# placa_v1.net
KiCad netlist of a schematic drawn in EAGLE
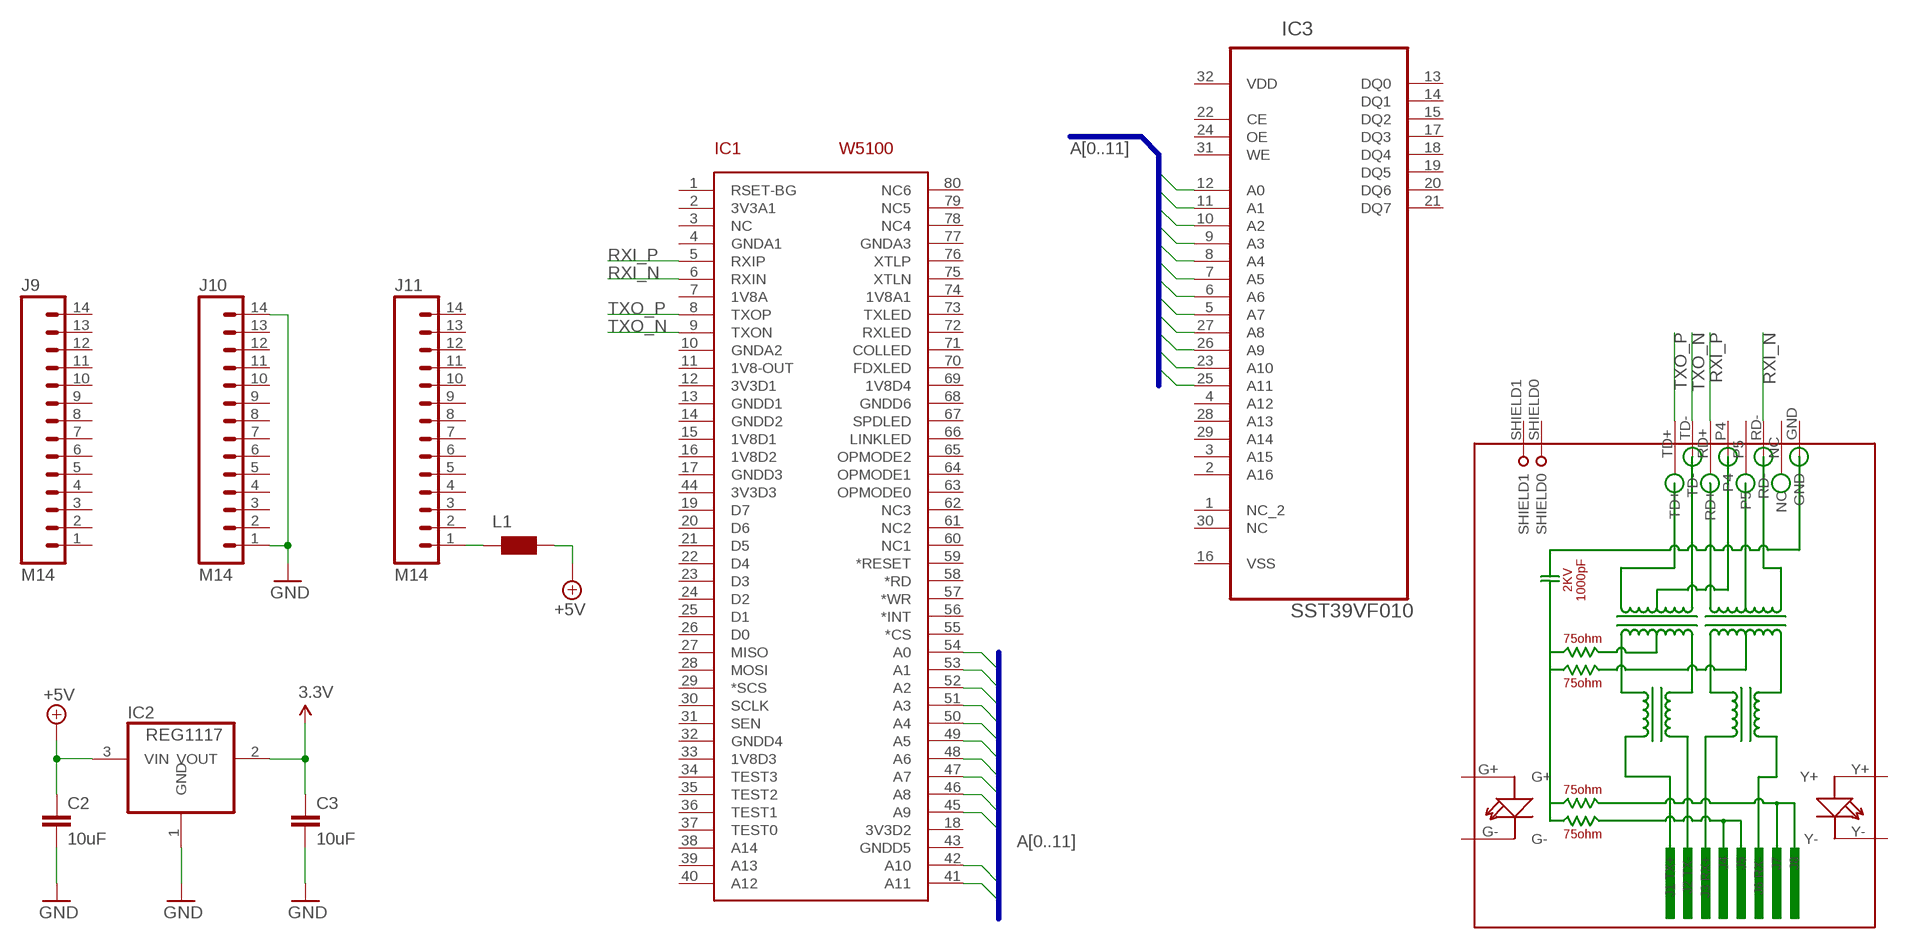
[diagram p0: schematic, sheet 1]

(export (version "E")
  (design (tool "Eeschema 10.0.6"))
  (components
    (comp (ref "C2")
      (value "10uF")
      (footprint "eagle-import:C0805K")
      (libsource (lib "eagle-import") (part "C-EUC0805K"))
    )
    (comp (ref "C3")
      (value "10uF")
      (footprint "eagle-import:C0805K")
      (libsource (lib "eagle-import") (part "C-EUC0805K"))
    )
    (comp (ref "IC1")
      (value "W5100")
      (footprint "eagle-import:SQFP-S-10X10-80")
      (libsource (lib "eagle-import") (part "W5100"))
    )
    (comp (ref "IC2")
      (value "REG1117")
      (footprint "eagle-import:SOT223")
      (libsource (lib "eagle-import") (part "REG1117"))
    )
    (comp (ref "IC3")
      (value "SST39VF010")
      (footprint "eagle-import:PLCC127P1244X1498X357-32N")
      (fields (field (name "MPN") "SST39VF010-70-4I-NHE"))
      (libsource (lib "eagle-import") (part "SST39VF010-70-4I-NHE"))
    )
    (comp (ref "J9")
      (value "M14")
      (footprint "eagle-import:1X14")
      (libsource (lib "eagle-import") (part "M14"))
    )
    (comp (ref "J10")
      (value "M14")
      (footprint "eagle-import:1X14")
      (libsource (lib "eagle-import") (part "M14"))
    )
    (comp (ref "J11")
      (value "M14")
      (footprint "eagle-import:1X14")
      (libsource (lib "eagle-import") (part "M14"))
    )
    (comp (ref "L1")
      (value "WE-CBF_0805")
      (footprint "eagle-import:0805")
      (libsource (lib "eagle-import") (part "WE-CBF_0805"))
    )
    (comp (ref "RJ1")
      (value "HR911105A")
      (footprint "eagle-import:HR911105A")
      (libsource (lib "eagle-import") (part "HR911105A"))
    )
  )
  (nets
    (net (code "1") (name "+5V") (class "Default")
      (node (ref "C2") (pin "1") (pinfunction "1_1") (pintype "passive"))
      (node (ref "IC2") (pin "3") (pinfunction "VIN_3") (pintype "input"))
      (node (ref "L1") (pin "2") (pinfunction "2_2") (pintype "passive"))
    )
    (net (code "2") (name "/1V8-OUT") (class "Default")
      (node (ref "IC1") (pin "11") (pinfunction "1V8-OUT_11") (pintype "power_in"))
    )
    (net (code "3") (name "/1V8A") (class "Default")
      (node (ref "IC1") (pin "7") (pinfunction "1V8A_7") (pintype "power_in"))
    )
    (net (code "4") (name "/1V8A1") (class "Default")
      (node (ref "IC1") (pin "74") (pinfunction "1V8A1_74") (pintype "power_in"))
    )
    (net (code "5") (name "/1V8D1") (class "Default")
      (node (ref "IC1") (pin "15") (pinfunction "1V8D1_15") (pintype "power_in"))
    )
    (net (code "6") (name "/1V8D2") (class "Default")
      (node (ref "IC1") (pin "16") (pinfunction "1V8D2_16") (pintype "power_in"))
    )
    (net (code "7") (name "/1V8D3") (class "Default")
      (node (ref "IC1") (pin "33") (pinfunction "1V8D3_33") (pintype "power_in"))
    )
    (net (code "8") (name "/1V8D4") (class "Default")
      (node (ref "IC1") (pin "69") (pinfunction "1V8D4_69") (pintype "power_in"))
    )
    (net (code "9") (name "/3V3A1") (class "Default")
      (node (ref "IC1") (pin "2") (pinfunction "3V3A1_2") (pintype "power_in"))
    )
    (net (code "10") (name "/3V3D1") (class "Default")
      (node (ref "IC1") (pin "12") (pinfunction "3V3D1_12") (pintype "power_in"))
    )
    (net (code "11") (name "/3V3D2") (class "Default")
      (node (ref "IC1") (pin "18") (pinfunction "3V3D2_18") (pintype "power_in"))
    )
    (net (code "12") (name "/3V3D3") (class "Default")
      (node (ref "IC1") (pin "44") (pinfunction "3V3D3_44") (pintype "power_in"))
    )
    (net (code "13") (name "/A0") (class "Default")
      (node (ref "IC1") (pin "54") (pinfunction "A0_54") (pintype "input"))
      (node (ref "IC3") (pin "12") (pinfunction "A0_12") (pintype "input"))
    )
    (net (code "14") (name "/A1") (class "Default")
      (node (ref "IC1") (pin "53") (pinfunction "A1_53") (pintype "input"))
      (node (ref "IC3") (pin "11") (pinfunction "A1_11") (pintype "input"))
    )
    (net (code "15") (name "/A2") (class "Default")
      (node (ref "IC1") (pin "52") (pinfunction "A2_52") (pintype "input"))
      (node (ref "IC3") (pin "10") (pinfunction "A2_10") (pintype "input"))
    )
    (net (code "16") (name "/A3") (class "Default")
      (node (ref "IC1") (pin "51") (pinfunction "A3_51") (pintype "input"))
      (node (ref "IC3") (pin "9") (pinfunction "A3_9") (pintype "input"))
    )
    (net (code "17") (name "/A4") (class "Default")
      (node (ref "IC1") (pin "50") (pinfunction "A4_50") (pintype "input"))
      (node (ref "IC3") (pin "8") (pinfunction "A4_8") (pintype "input"))
    )
    (net (code "18") (name "/A5") (class "Default")
      (node (ref "IC1") (pin "49") (pinfunction "A5_49") (pintype "input"))
      (node (ref "IC3") (pin "7") (pinfunction "A5_7") (pintype "input"))
    )
    (net (code "19") (name "/A6") (class "Default")
      (node (ref "IC1") (pin "48") (pinfunction "A6_48") (pintype "input"))
      (node (ref "IC3") (pin "6") (pinfunction "A6_6") (pintype "input"))
    )
    (net (code "20") (name "/A7") (class "Default")
      (node (ref "IC1") (pin "47") (pinfunction "A7_47") (pintype "input"))
      (node (ref "IC3") (pin "5") (pinfunction "A7_5") (pintype "input"))
    )
    (net (code "21") (name "/A8") (class "Default")
      (node (ref "IC1") (pin "46") (pinfunction "A8_46") (pintype "input"))
      (node (ref "IC3") (pin "27") (pinfunction "A8_27") (pintype "input"))
    )
    (net (code "22") (name "/A9") (class "Default")
      (node (ref "IC1") (pin "45") (pinfunction "A9_45") (pintype "input"))
      (node (ref "IC3") (pin "26") (pinfunction "A9_26") (pintype "input"))
    )
    (net (code "23") (name "/A10") (class "Default")
      (node (ref "IC1") (pin "42") (pinfunction "A10_42") (pintype "input"))
      (node (ref "IC3") (pin "23") (pinfunction "A10_23") (pintype "input"))
    )
    (net (code "24") (name "/A11") (class "Default")
      (node (ref "IC1") (pin "41") (pinfunction "A11_41") (pintype "input"))
      (node (ref "IC3") (pin "25") (pinfunction "A11_25") (pintype "input"))
    )
    (net (code "26") (name "/GNDA1") (class "Default")
      (node (ref "IC1") (pin "4") (pinfunction "GNDA1_4") (pintype "power_in"))
    )
    (net (code "27") (name "/GNDA2") (class "Default")
      (node (ref "IC1") (pin "10") (pinfunction "GNDA2_10") (pintype "power_in"))
    )
    (net (code "28") (name "/GNDA3") (class "Default")
      (node (ref "IC1") (pin "77") (pinfunction "GNDA3_77") (pintype "power_in"))
    )
    (net (code "29") (name "/GNDD1") (class "Default")
      (node (ref "IC1") (pin "13") (pinfunction "GNDD1_13") (pintype "power_in"))
    )
    (net (code "30") (name "/GNDD2") (class "Default")
      (node (ref "IC1") (pin "14") (pinfunction "GNDD2_14") (pintype "power_in"))
    )
    (net (code "31") (name "/GNDD3") (class "Default")
      (node (ref "IC1") (pin "17") (pinfunction "GNDD3_17") (pintype "power_in"))
    )
    (net (code "32") (name "/GNDD4") (class "Default")
      (node (ref "IC1") (pin "32") (pinfunction "GNDD4_32") (pintype "power_in"))
    )
    (net (code "33") (name "/GNDD5") (class "Default")
      (node (ref "IC1") (pin "43") (pinfunction "GNDD5_43") (pintype "power_in"))
    )
    (net (code "34") (name "/GNDD6") (class "Default")
      (node (ref "IC1") (pin "68") (pinfunction "GNDD6_68") (pintype "power_in"))
    )
    (net (code "35") (name "/RXI_N") (class "Default")
      (node (ref "IC1") (pin "6") (pinfunction "RXIN_6") (pintype "input"))
      (node (ref "RJ1") (pin "RD-") (pinfunction "RD-_RD-") (pintype "bidirectional"))
    )
    (net (code "36") (name "/RXI_P") (class "Default")
      (node (ref "IC1") (pin "5") (pinfunction "RXIP_5") (pintype "input"))
      (node (ref "RJ1") (pin "RD+") (pinfunction "RD+_RD+") (pintype "bidirectional"))
    )
    (net (code "37") (name "/TXO_N") (class "Default")
      (node (ref "IC1") (pin "9") (pinfunction "TXON_9") (pintype "output"))
      (node (ref "RJ1") (pin "TD-") (pinfunction "TD-_TD-") (pintype "bidirectional"))
    )
    (net (code "38") (name "/TXO_P") (class "Default")
      (node (ref "IC1") (pin "8") (pinfunction "TXOP_8") (pintype "output"))
      (node (ref "RJ1") (pin "TD+") (pinfunction "TD+_TD+") (pintype "bidirectional"))
    )
    (net (code "39") (name "/VDD") (class "Default")
      (node (ref "IC3") (pin "32") (pinfunction "VDD_32") (pintype "power_in"))
    )
    (net (code "40") (name "3.3V") (class "Default")
      (node (ref "C3") (pin "1") (pinfunction "1_1") (pintype "passive"))
      (node (ref "IC2") (pin "2") (pinfunction "VOUT_2") (pintype "output"))
    )
    (net (code "41") (name "GND") (class "Default")
      (node (ref "C2") (pin "2") (pinfunction "2_2") (pintype "passive"))
      (node (ref "C3") (pin "2") (pinfunction "2_2") (pintype "passive"))
      (node (ref "IC2") (pin "1") (pinfunction "GND_1") (pintype "power_in"))
      (node (ref "J10") (pin "1") (pinfunction "1_1") (pintype "passive"))
      (node (ref "J10") (pin "14") (pinfunction "14_14") (pintype "passive"))
    )
    (net (code "42") (name "Net-(J11-Pad1)") (class "Default")
      (node (ref "J11") (pin "1") (pinfunction "1_1") (pintype "passive"))
      (node (ref "L1") (pin "1") (pinfunction "1_1") (pintype "passive"))
    )
    (net (code "43") (name "unconnected-(IC1-*CS-Pad55)") (class "Default")
      (node (ref "IC1") (pin "55") (pinfunction "*CS_55") (pintype "input"))
    )
    (net (code "44") (name "unconnected-(IC1-*INT-Pad56)") (class "Default")
      (node (ref "IC1") (pin "56") (pinfunction "*INT_56") (pintype "input"))
    )
    (net (code "45") (name "unconnected-(IC1-*RD-Pad58)") (class "Default")
      (node (ref "IC1") (pin "58") (pinfunction "*RD_58") (pintype "input"))
    )
    (net (code "46") (name "unconnected-(IC1-*RESET-Pad59)") (class "Default")
      (node (ref "IC1") (pin "59") (pinfunction "*RESET_59") (pintype "input"))
    )
    (net (code "47") (name "unconnected-(IC1-*SCS-Pad29)") (class "Default")
      (node (ref "IC1") (pin "29") (pinfunction "*SCS_29") (pintype "input"))
    )
    (net (code "48") (name "unconnected-(IC1-*WR-Pad57)") (class "Default")
      (node (ref "IC1") (pin "57") (pinfunction "*WR_57") (pintype "input"))
    )
    (net (code "49") (name "unconnected-(IC1-A12-Pad40)") (class "Default")
      (node (ref "IC1") (pin "40") (pinfunction "A12_40") (pintype "input"))
    )
    (net (code "50") (name "unconnected-(IC1-A13-Pad39)") (class "Default")
      (node (ref "IC1") (pin "39") (pinfunction "A13_39") (pintype "input"))
    )
    (net (code "51") (name "unconnected-(IC1-A14-Pad38)") (class "Default")
      (node (ref "IC1") (pin "38") (pinfunction "A14_38") (pintype "input"))
    )
    (net (code "52") (name "unconnected-(IC1-COLLED-Pad71)") (class "Default")
      (node (ref "IC1") (pin "71") (pinfunction "COLLED_71") (pintype "output"))
    )
    (net (code "53") (name "unconnected-(IC1-D0-Pad26)") (class "Default")
      (node (ref "IC1") (pin "26") (pinfunction "D0_26") (pintype "input"))
    )
    (net (code "54") (name "unconnected-(IC1-D1-Pad25)") (class "Default")
      (node (ref "IC1") (pin "25") (pinfunction "D1_25") (pintype "input"))
    )
    (net (code "55") (name "unconnected-(IC1-D2-Pad24)") (class "Default")
      (node (ref "IC1") (pin "24") (pinfunction "D2_24") (pintype "input"))
    )
    (net (code "56") (name "unconnected-(IC1-D3-Pad23)") (class "Default")
      (node (ref "IC1") (pin "23") (pinfunction "D3_23") (pintype "input"))
    )
    (net (code "57") (name "unconnected-(IC1-D4-Pad22)") (class "Default")
      (node (ref "IC1") (pin "22") (pinfunction "D4_22") (pintype "input"))
    )
    (net (code "58") (name "unconnected-(IC1-D5-Pad21)") (class "Default")
      (node (ref "IC1") (pin "21") (pinfunction "D5_21") (pintype "input"))
    )
    (net (code "59") (name "unconnected-(IC1-D6-Pad20)") (class "Default")
      (node (ref "IC1") (pin "20") (pinfunction "D6_20") (pintype "input"))
    )
    (net (code "60") (name "unconnected-(IC1-D7-Pad19)") (class "Default")
      (node (ref "IC1") (pin "19") (pinfunction "D7_19") (pintype "input"))
    )
    (net (code "61") (name "unconnected-(IC1-FDXLED-Pad70)") (class "Default")
      (node (ref "IC1") (pin "70") (pinfunction "FDXLED_70") (pintype "output"))
    )
    (net (code "62") (name "unconnected-(IC1-LINKLED-Pad66)") (class "Default")
      (node (ref "IC1") (pin "66") (pinfunction "LINKLED_66") (pintype "output"))
    )
    (net (code "63") (name "unconnected-(IC1-MISO-Pad27)") (class "Default")
      (node (ref "IC1") (pin "27") (pinfunction "MISO_27") (pintype "input"))
    )
    (net (code "64") (name "unconnected-(IC1-MOSI-Pad28)") (class "Default")
      (node (ref "IC1") (pin "28") (pinfunction "MOSI_28") (pintype "output"))
    )
    (net (code "65") (name "unconnected-(IC1-NC-Pad3)") (class "Default")
      (node (ref "IC1") (pin "3") (pinfunction "NC_3") (pintype "no_connect"))
    )
    (net (code "66") (name "unconnected-(IC1-NC1-Pad60)") (class "Default")
      (node (ref "IC1") (pin "60") (pinfunction "NC1_60") (pintype "no_connect"))
    )
    (net (code "67") (name "unconnected-(IC1-NC2-Pad61)") (class "Default")
      (node (ref "IC1") (pin "61") (pinfunction "NC2_61") (pintype "no_connect"))
    )
    (net (code "68") (name "unconnected-(IC1-NC3-Pad62)") (class "Default")
      (node (ref "IC1") (pin "62") (pinfunction "NC3_62") (pintype "no_connect"))
    )
    (net (code "69") (name "unconnected-(IC1-NC4-Pad78)") (class "Default")
      (node (ref "IC1") (pin "78") (pinfunction "NC4_78") (pintype "no_connect"))
    )
    (net (code "70") (name "unconnected-(IC1-NC5-Pad79)") (class "Default")
      (node (ref "IC1") (pin "79") (pinfunction "NC5_79") (pintype "no_connect"))
    )
    (net (code "71") (name "unconnected-(IC1-NC6-Pad80)") (class "Default")
      (node (ref "IC1") (pin "80") (pinfunction "NC6_80") (pintype "no_connect"))
    )
    (net (code "72") (name "unconnected-(IC1-OPMODE0-Pad63)") (class "Default")
      (node (ref "IC1") (pin "63") (pinfunction "OPMODE0_63") (pintype "input"))
    )
    (net (code "73") (name "unconnected-(IC1-OPMODE1-Pad64)") (class "Default")
      (node (ref "IC1") (pin "64") (pinfunction "OPMODE1_64") (pintype "input"))
    )
    (net (code "74") (name "unconnected-(IC1-OPMODE2-Pad65)") (class "Default")
      (node (ref "IC1") (pin "65") (pinfunction "OPMODE2_65") (pintype "input"))
    )
    (net (code "75") (name "unconnected-(IC1-RSET-BG-Pad1)") (class "Default")
      (node (ref "IC1") (pin "1") (pinfunction "RSET-BG_1") (pintype "input"))
    )
    (net (code "76") (name "unconnected-(IC1-RXLED-Pad72)") (class "Default")
      (node (ref "IC1") (pin "72") (pinfunction "RXLED_72") (pintype "output"))
    )
    (net (code "77") (name "unconnected-(IC1-SCLK-Pad30)") (class "Default")
      (node (ref "IC1") (pin "30") (pinfunction "SCLK_30") (pintype "input"))
    )
    (net (code "78") (name "unconnected-(IC1-SEN-Pad31)") (class "Default")
      (node (ref "IC1") (pin "31") (pinfunction "SEN_31") (pintype "input"))
    )
    (net (code "79") (name "unconnected-(IC1-SPDLED-Pad67)") (class "Default")
      (node (ref "IC1") (pin "67") (pinfunction "SPDLED_67") (pintype "output"))
    )
    (net (code "80") (name "unconnected-(IC1-TEST0-Pad37)") (class "Default")
      (node (ref "IC1") (pin "37") (pinfunction "TEST0_37") (pintype "input"))
    )
    (net (code "81") (name "unconnected-(IC1-TEST1-Pad36)") (class "Default")
      (node (ref "IC1") (pin "36") (pinfunction "TEST1_36") (pintype "input"))
    )
    (net (code "82") (name "unconnected-(IC1-TEST2-Pad35)") (class "Default")
      (node (ref "IC1") (pin "35") (pinfunction "TEST2_35") (pintype "input"))
    )
    (net (code "83") (name "unconnected-(IC1-TEST3-Pad34)") (class "Default")
      (node (ref "IC1") (pin "34") (pinfunction "TEST3_34") (pintype "input"))
    )
    (net (code "84") (name "unconnected-(IC1-TXLED-Pad73)") (class "Default")
      (node (ref "IC1") (pin "73") (pinfunction "TXLED_73") (pintype "output"))
    )
    (net (code "85") (name "unconnected-(IC1-XTLN-Pad75)") (class "Default")
      (node (ref "IC1") (pin "75") (pinfunction "XTLN_75") (pintype "output"))
    )
    (net (code "86") (name "unconnected-(IC1-XTLP-Pad76)") (class "Default")
      (node (ref "IC1") (pin "76") (pinfunction "XTLP_76") (pintype "output"))
    )
    (net (code "87") (name "unconnected-(IC3-A12-Pad4)") (class "Default")
      (node (ref "IC3") (pin "4") (pinfunction "A12_4") (pintype "input"))
    )
    (net (code "88") (name "unconnected-(IC3-A13-Pad28)") (class "Default")
      (node (ref "IC3") (pin "28") (pinfunction "A13_28") (pintype "input"))
    )
    (net (code "89") (name "unconnected-(IC3-A14-Pad29)") (class "Default")
      (node (ref "IC3") (pin "29") (pinfunction "A14_29") (pintype "input"))
    )
    (net (code "90") (name "unconnected-(IC3-A15-Pad3)") (class "Default")
      (node (ref "IC3") (pin "3") (pinfunction "A15_3") (pintype "input"))
    )
    (net (code "91") (name "unconnected-(IC3-A16-Pad2)") (class "Default")
      (node (ref "IC3") (pin "2") (pinfunction "A16_2") (pintype "input"))
    )
    (net (code "92") (name "unconnected-(IC3-CE-Pad22)") (class "Default")
      (node (ref "IC3") (pin "22") (pinfunction "CE_22") (pintype "input"))
    )
    (net (code "93") (name "unconnected-(IC3-DQ0-Pad13)") (class "Default")
      (node (ref "IC3") (pin "13") (pinfunction "DQ0_13") (pintype "output"))
    )
    (net (code "94") (name "unconnected-(IC3-DQ1-Pad14)") (class "Default")
      (node (ref "IC3") (pin "14") (pinfunction "DQ1_14") (pintype "output"))
    )
    (net (code "95") (name "unconnected-(IC3-DQ2-Pad15)") (class "Default")
      (node (ref "IC3") (pin "15") (pinfunction "DQ2_15") (pintype "output"))
    )
    (net (code "96") (name "unconnected-(IC3-DQ3-Pad17)") (class "Default")
      (node (ref "IC3") (pin "17") (pinfunction "DQ3_17") (pintype "output"))
    )
    (net (code "97") (name "unconnected-(IC3-DQ4-Pad18)") (class "Default")
      (node (ref "IC3") (pin "18") (pinfunction "DQ4_18") (pintype "output"))
    )
    (net (code "98") (name "unconnected-(IC3-DQ5-Pad19)") (class "Default")
      (node (ref "IC3") (pin "19") (pinfunction "DQ5_19") (pintype "output"))
    )
    (net (code "99") (name "unconnected-(IC3-DQ6-Pad20)") (class "Default")
      (node (ref "IC3") (pin "20") (pinfunction "DQ6_20") (pintype "output"))
    )
    (net (code "100") (name "unconnected-(IC3-DQ7-Pad21)") (class "Default")
      (node (ref "IC3") (pin "21") (pinfunction "DQ7_21") (pintype "output"))
    )
    (net (code "101") (name "unconnected-(IC3-NC-Pad30)") (class "Default")
      (node (ref "IC3") (pin "30") (pinfunction "NC_30") (pintype "no_connect"))
    )
    (net (code "102") (name "unconnected-(IC3-NC_2-Pad1)") (class "Default")
      (node (ref "IC3") (pin "1") (pinfunction "NC_2_1") (pintype "no_connect"))
    )
    (net (code "103") (name "unconnected-(IC3-OE-Pad24)") (class "Default")
      (node (ref "IC3") (pin "24") (pinfunction "OE_24") (pintype "input"))
    )
    (net (code "104") (name "unconnected-(IC3-VSS-Pad16)") (class "Default")
      (node (ref "IC3") (pin "16") (pinfunction "VSS_16") (pintype "passive"))
    )
    (net (code "105") (name "unconnected-(IC3-WE-Pad31)") (class "Default")
      (node (ref "IC3") (pin "31") (pinfunction "WE_31") (pintype "input"))
    )
    (net (code "106") (name "unconnected-(J9-Pad1)") (class "Default")
      (node (ref "J9") (pin "1") (pinfunction "1_1") (pintype "passive"))
    )
    (net (code "107") (name "unconnected-(J9-Pad2)") (class "Default")
      (node (ref "J9") (pin "2") (pinfunction "2_2") (pintype "passive"))
    )
    (net (code "108") (name "unconnected-(J9-Pad3)") (class "Default")
      (node (ref "J9") (pin "3") (pinfunction "3_3") (pintype "passive"))
    )
    (net (code "109") (name "unconnected-(J9-Pad4)") (class "Default")
      (node (ref "J9") (pin "4") (pinfunction "4_4") (pintype "passive"))
    )
    (net (code "110") (name "unconnected-(J9-Pad5)") (class "Default")
      (node (ref "J9") (pin "5") (pinfunction "5_5") (pintype "passive"))
    )
    (net (code "111") (name "unconnected-(J9-Pad6)") (class "Default")
      (node (ref "J9") (pin "6") (pinfunction "6_6") (pintype "passive"))
    )
    (net (code "112") (name "unconnected-(J9-Pad7)") (class "Default")
      (node (ref "J9") (pin "7") (pinfunction "7_7") (pintype "passive"))
    )
    (net (code "113") (name "unconnected-(J9-Pad8)") (class "Default")
      (node (ref "J9") (pin "8") (pinfunction "8_8") (pintype "passive"))
    )
    (net (code "114") (name "unconnected-(J9-Pad9)") (class "Default")
      (node (ref "J9") (pin "9") (pinfunction "9_9") (pintype "passive"))
    )
    (net (code "115") (name "unconnected-(J9-Pad10)") (class "Default")
      (node (ref "J9") (pin "10") (pinfunction "10_10") (pintype "passive"))
    )
    (net (code "116") (name "unconnected-(J9-Pad11)") (class "Default")
      (node (ref "J9") (pin "11") (pinfunction "11_11") (pintype "passive"))
    )
    (net (code "117") (name "unconnected-(J9-Pad12)") (class "Default")
      (node (ref "J9") (pin "12") (pinfunction "12_12") (pintype "passive"))
    )
    (net (code "118") (name "unconnected-(J9-Pad13)") (class "Default")
      (node (ref "J9") (pin "13") (pinfunction "13_13") (pintype "passive"))
    )
    (net (code "119") (name "unconnected-(J9-Pad14)") (class "Default")
      (node (ref "J9") (pin "14") (pinfunction "14_14") (pintype "passive"))
    )
    (net (code "120") (name "unconnected-(J10-Pad2)") (class "Default")
      (node (ref "J10") (pin "2") (pinfunction "2_2") (pintype "passive"))
    )
    (net (code "121") (name "unconnected-(J10-Pad3)") (class "Default")
      (node (ref "J10") (pin "3") (pinfunction "3_3") (pintype "passive"))
    )
    (net (code "122") (name "unconnected-(J10-Pad4)") (class "Default")
      (node (ref "J10") (pin "4") (pinfunction "4_4") (pintype "passive"))
    )
    (net (code "123") (name "unconnected-(J10-Pad5)") (class "Default")
      (node (ref "J10") (pin "5") (pinfunction "5_5") (pintype "passive"))
    )
    (net (code "124") (name "unconnected-(J10-Pad6)") (class "Default")
      (node (ref "J10") (pin "6") (pinfunction "6_6") (pintype "passive"))
    )
    (net (code "125") (name "unconnected-(J10-Pad7)") (class "Default")
      (node (ref "J10") (pin "7") (pinfunction "7_7") (pintype "passive"))
    )
    (net (code "126") (name "unconnected-(J10-Pad8)") (class "Default")
      (node (ref "J10") (pin "8") (pinfunction "8_8") (pintype "passive"))
    )
    (net (code "127") (name "unconnected-(J10-Pad9)") (class "Default")
      (node (ref "J10") (pin "9") (pinfunction "9_9") (pintype "passive"))
    )
    (net (code "128") (name "unconnected-(J10-Pad10)") (class "Default")
      (node (ref "J10") (pin "10") (pinfunction "10_10") (pintype "passive"))
    )
    (net (code "129") (name "unconnected-(J10-Pad11)") (class "Default")
      (node (ref "J10") (pin "11") (pinfunction "11_11") (pintype "passive"))
    )
    (net (code "130") (name "unconnected-(J10-Pad12)") (class "Default")
      (node (ref "J10") (pin "12") (pinfunction "12_12") (pintype "passive"))
    )
    (net (code "131") (name "unconnected-(J10-Pad13)") (class "Default")
      (node (ref "J10") (pin "13") (pinfunction "13_13") (pintype "passive"))
    )
    (net (code "132") (name "unconnected-(J11-Pad2)") (class "Default")
      (node (ref "J11") (pin "2") (pinfunction "2_2") (pintype "passive"))
    )
    (net (code "133") (name "unconnected-(J11-Pad3)") (class "Default")
      (node (ref "J11") (pin "3") (pinfunction "3_3") (pintype "passive"))
    )
    (net (code "134") (name "unconnected-(J11-Pad4)") (class "Default")
      (node (ref "J11") (pin "4") (pinfunction "4_4") (pintype "passive"))
    )
    (net (code "135") (name "unconnected-(J11-Pad5)") (class "Default")
      (node (ref "J11") (pin "5") (pinfunction "5_5") (pintype "passive"))
    )
    (net (code "136") (name "unconnected-(J11-Pad6)") (class "Default")
      (node (ref "J11") (pin "6") (pinfunction "6_6") (pintype "passive"))
    )
    (net (code "137") (name "unconnected-(J11-Pad7)") (class "Default")
      (node (ref "J11") (pin "7") (pinfunction "7_7") (pintype "passive"))
    )
    (net (code "138") (name "unconnected-(J11-Pad8)") (class "Default")
      (node (ref "J11") (pin "8") (pinfunction "8_8") (pintype "passive"))
    )
    (net (code "139") (name "unconnected-(J11-Pad9)") (class "Default")
      (node (ref "J11") (pin "9") (pinfunction "9_9") (pintype "passive"))
    )
    (net (code "140") (name "unconnected-(J11-Pad10)") (class "Default")
      (node (ref "J11") (pin "10") (pinfunction "10_10") (pintype "passive"))
    )
    (net (code "141") (name "unconnected-(J11-Pad11)") (class "Default")
      (node (ref "J11") (pin "11") (pinfunction "11_11") (pintype "passive"))
    )
    (net (code "142") (name "unconnected-(J11-Pad12)") (class "Default")
      (node (ref "J11") (pin "12") (pinfunction "12_12") (pintype "passive"))
    )
    (net (code "143") (name "unconnected-(J11-Pad13)") (class "Default")
      (node (ref "J11") (pin "13") (pinfunction "13_13") (pintype "passive"))
    )
    (net (code "144") (name "unconnected-(J11-Pad14)") (class "Default")
      (node (ref "J11") (pin "14") (pinfunction "14_14") (pintype "passive"))
    )
    (net (code "145") (name "unconnected-(RJ1-PadG+)") (class "Default")
      (node (ref "RJ1") (pin "G+") (pinfunction "G+_G+") (pintype "bidirectional"))
    )
    (net (code "146") (name "unconnected-(RJ1-PadG-)") (class "Default")
      (node (ref "RJ1") (pin "G-") (pinfunction "G-_G-") (pintype "bidirectional"))
    )
    (net (code "147") (name "unconnected-(RJ1-PadGND)") (class "Default")
      (node (ref "RJ1") (pin "GND") (pinfunction "GND_GND") (pintype "bidirectional"))
    )
    (net (code "148") (name "unconnected-(RJ1-PadNC)") (class "Default")
      (node (ref "RJ1") (pin "NC") (pinfunction "NC_NC") (pintype "bidirectional"))
    )
    (net (code "149") (name "unconnected-(RJ1-PadP4)") (class "Default")
      (node (ref "RJ1") (pin "P4") (pinfunction "P4_P4") (pintype "bidirectional"))
    )
    (net (code "150") (name "unconnected-(RJ1-PadP5)") (class "Default")
      (node (ref "RJ1") (pin "P5") (pinfunction "P5_P5") (pintype "bidirectional"))
    )
    (net (code "151") (name "unconnected-(RJ1-PadSHIELD0)") (class "Default")
      (node (ref "RJ1") (pin "SHIELD0") (pinfunction "SHIELD0_SHIELD0") (pintype "bidirectional"))
    )
    (net (code "152") (name "unconnected-(RJ1-PadSHIELD1)") (class "Default")
      (node (ref "RJ1") (pin "SHIELD1") (pinfunction "SHIELD1_SHIELD1") (pintype "bidirectional"))
    )
    (net (code "153") (name "unconnected-(RJ1-PadY+)") (class "Default")
      (node (ref "RJ1") (pin "Y+") (pinfunction "Y+_Y+") (pintype "bidirectional"))
    )
    (net (code "154") (name "unconnected-(RJ1-PadY-)") (class "Default")
      (node (ref "RJ1") (pin "Y-") (pinfunction "Y-_Y-") (pintype "bidirectional"))
    )
  )
)
